# 555.net
KiCad netlist of a schematic drawn in Altium Designer
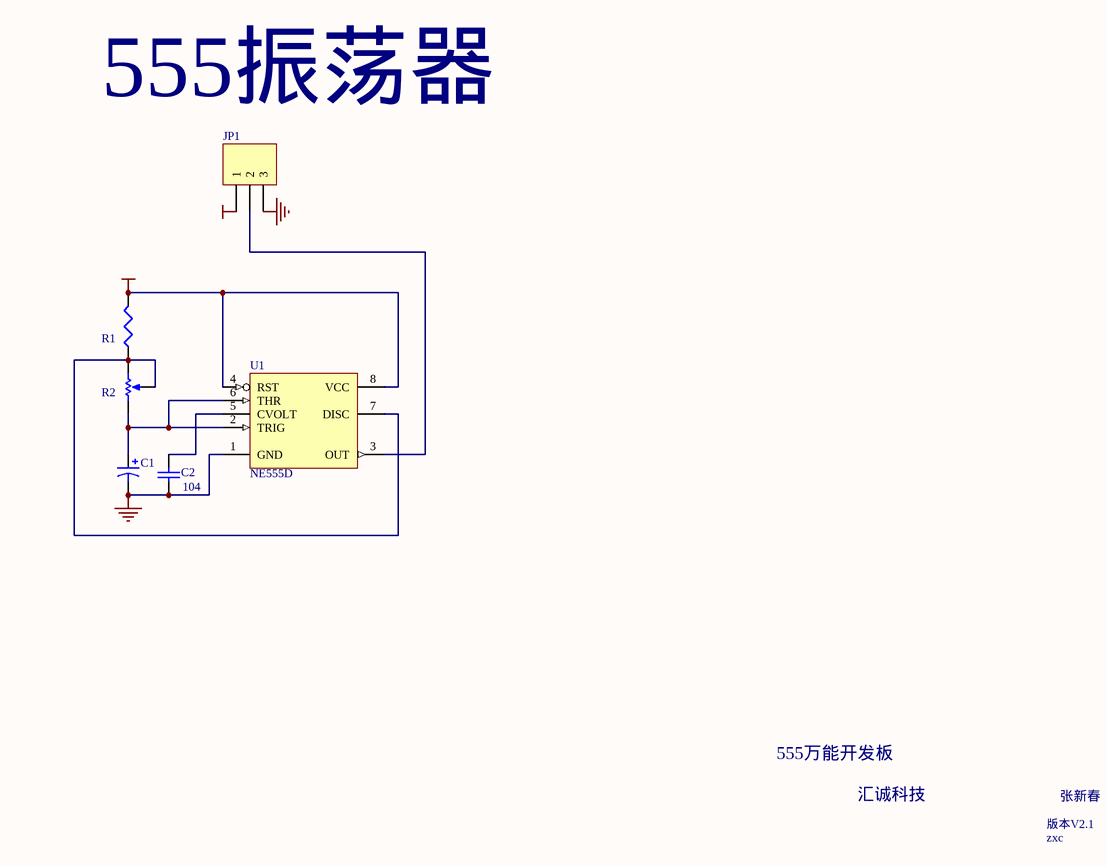
[diagram p0: 555振荡器.SchDoc]

(export (version "E")
  (design (tool "Eeschema 10.0.6"))
  (components
    (comp (ref "C1")
      (value "~")
      (footprint "C-DJ-4")
      (description "Polarized Capacitor (Radial)")
      (fields (field (name "PUBLISHER") "Altium Limited"))
      (libsource (lib "Miscellaneous Devices") (part "Cap Pol1"))
    )
    (comp (ref "C2")
      (value "104")
      (footprint "C1608-0603")
      (description "Capacitor (Semiconductor SIM Model)")
      (fields (field (name "PUBLISHER") "Altium Limited"))
      (libsource (lib "Miscellaneous Devices") (part "Cap Semi"))
    )
    (comp (ref "JP1")
      (value "~")
      (footprint "HDR1X3")
      (description "Header, 3-Pin")
      (fields (field (name "PUBLISHER") "Altium Limited"))
      (libsource (lib "Miscellaneous Connectors") (part "Header 3"))
    )
    (comp (ref "R1")
      (value "~")
      (footprint "C1608-0603")
      (description "Resistor")
      (fields (field (name "PUBLISHER") "Altium Limited"))
      (libsource (lib "Miscellaneous Devices") (part "Res3"))
    )
    (comp (ref "R2")
      (value "~")
      (footprint "SIP3-D")
      (description "Potentiometer")
      (fields (field (name "PUBLISHER") "Altium Limited"))
      (libsource (lib "Miscellaneous Devices") (part "RPot"))
    )
    (comp (ref "U1")
      (value "NE555D")
      (footprint "CDFP-8")
      (description "Precision Timer")
      (fields (field (name "MANUFACTURER") "Texas Instruments") (field (name "PUBLISHER") "Altium Limited"))
      (libsource (lib "TI Analog Timer Circuit") (part "NE555D"))
    )
  )
  (nets
    (net (code "1") (name "GND") (class "Default")
      (node (ref "C1") (pin "2") (pinfunction "2_2") (pintype "passive"))
      (node (ref "C2") (pin "2") (pinfunction "2_2") (pintype "passive"))
      (node (ref "JP1") (pin "3") (pinfunction "3_3") (pintype "passive"))
      (node (ref "U1") (pin "1") (pinfunction "GND_1") (pintype "power_in"))
    )
    (net (code "2") (name "Net-(R2-BOT)") (class "Default")
      (node (ref "R1") (pin "1") (pinfunction "1_1") (pintype "passive"))
      (node (ref "R2") (pin "2") (pinfunction "BOT_2") (pintype "passive"))
      (node (ref "R2") (pin "3") (pinfunction "TAP_3") (pintype "passive"))
      (node (ref "U1") (pin "7") (pinfunction "DISC_7") (pintype "open_collector"))
    )
    (net (code "3") (name "Net-(R2-TOP)") (class "Default")
      (node (ref "C1") (pin "1") (pinfunction "1_1") (pintype "passive"))
      (node (ref "R2") (pin "1") (pinfunction "TOP_1") (pintype "passive"))
      (node (ref "U1") (pin "2") (pinfunction "TRIG_2") (pintype "input"))
      (node (ref "U1") (pin "6") (pinfunction "THR_6") (pintype "input"))
    )
    (net (code "4") (name "Net-(U1-CVOLT)") (class "Default")
      (node (ref "C2") (pin "1") (pinfunction "1_1") (pintype "passive"))
      (node (ref "U1") (pin "5") (pinfunction "CVOLT_5") (pintype "passive"))
    )
    (net (code "5") (name "Net-(U1-OUT)") (class "Default")
      (node (ref "JP1") (pin "2") (pinfunction "2_2") (pintype "passive"))
      (node (ref "U1") (pin "3") (pinfunction "OUT_3") (pintype "output"))
    )
    (net (code "6") (name "VCC") (class "Default")
      (node (ref "JP1") (pin "1") (pinfunction "1_1") (pintype "passive"))
      (node (ref "R1") (pin "2") (pinfunction "2_2") (pintype "passive"))
      (node (ref "U1") (pin "4") (pinfunction "RST_4") (pintype "input"))
      (node (ref "U1") (pin "8") (pinfunction "VCC_8") (pintype "power_in"))
    )
  )
)
